# Onion_Omega_Debug_PCB.net
KiCad netlist of a schematic drawn in Altium Designer
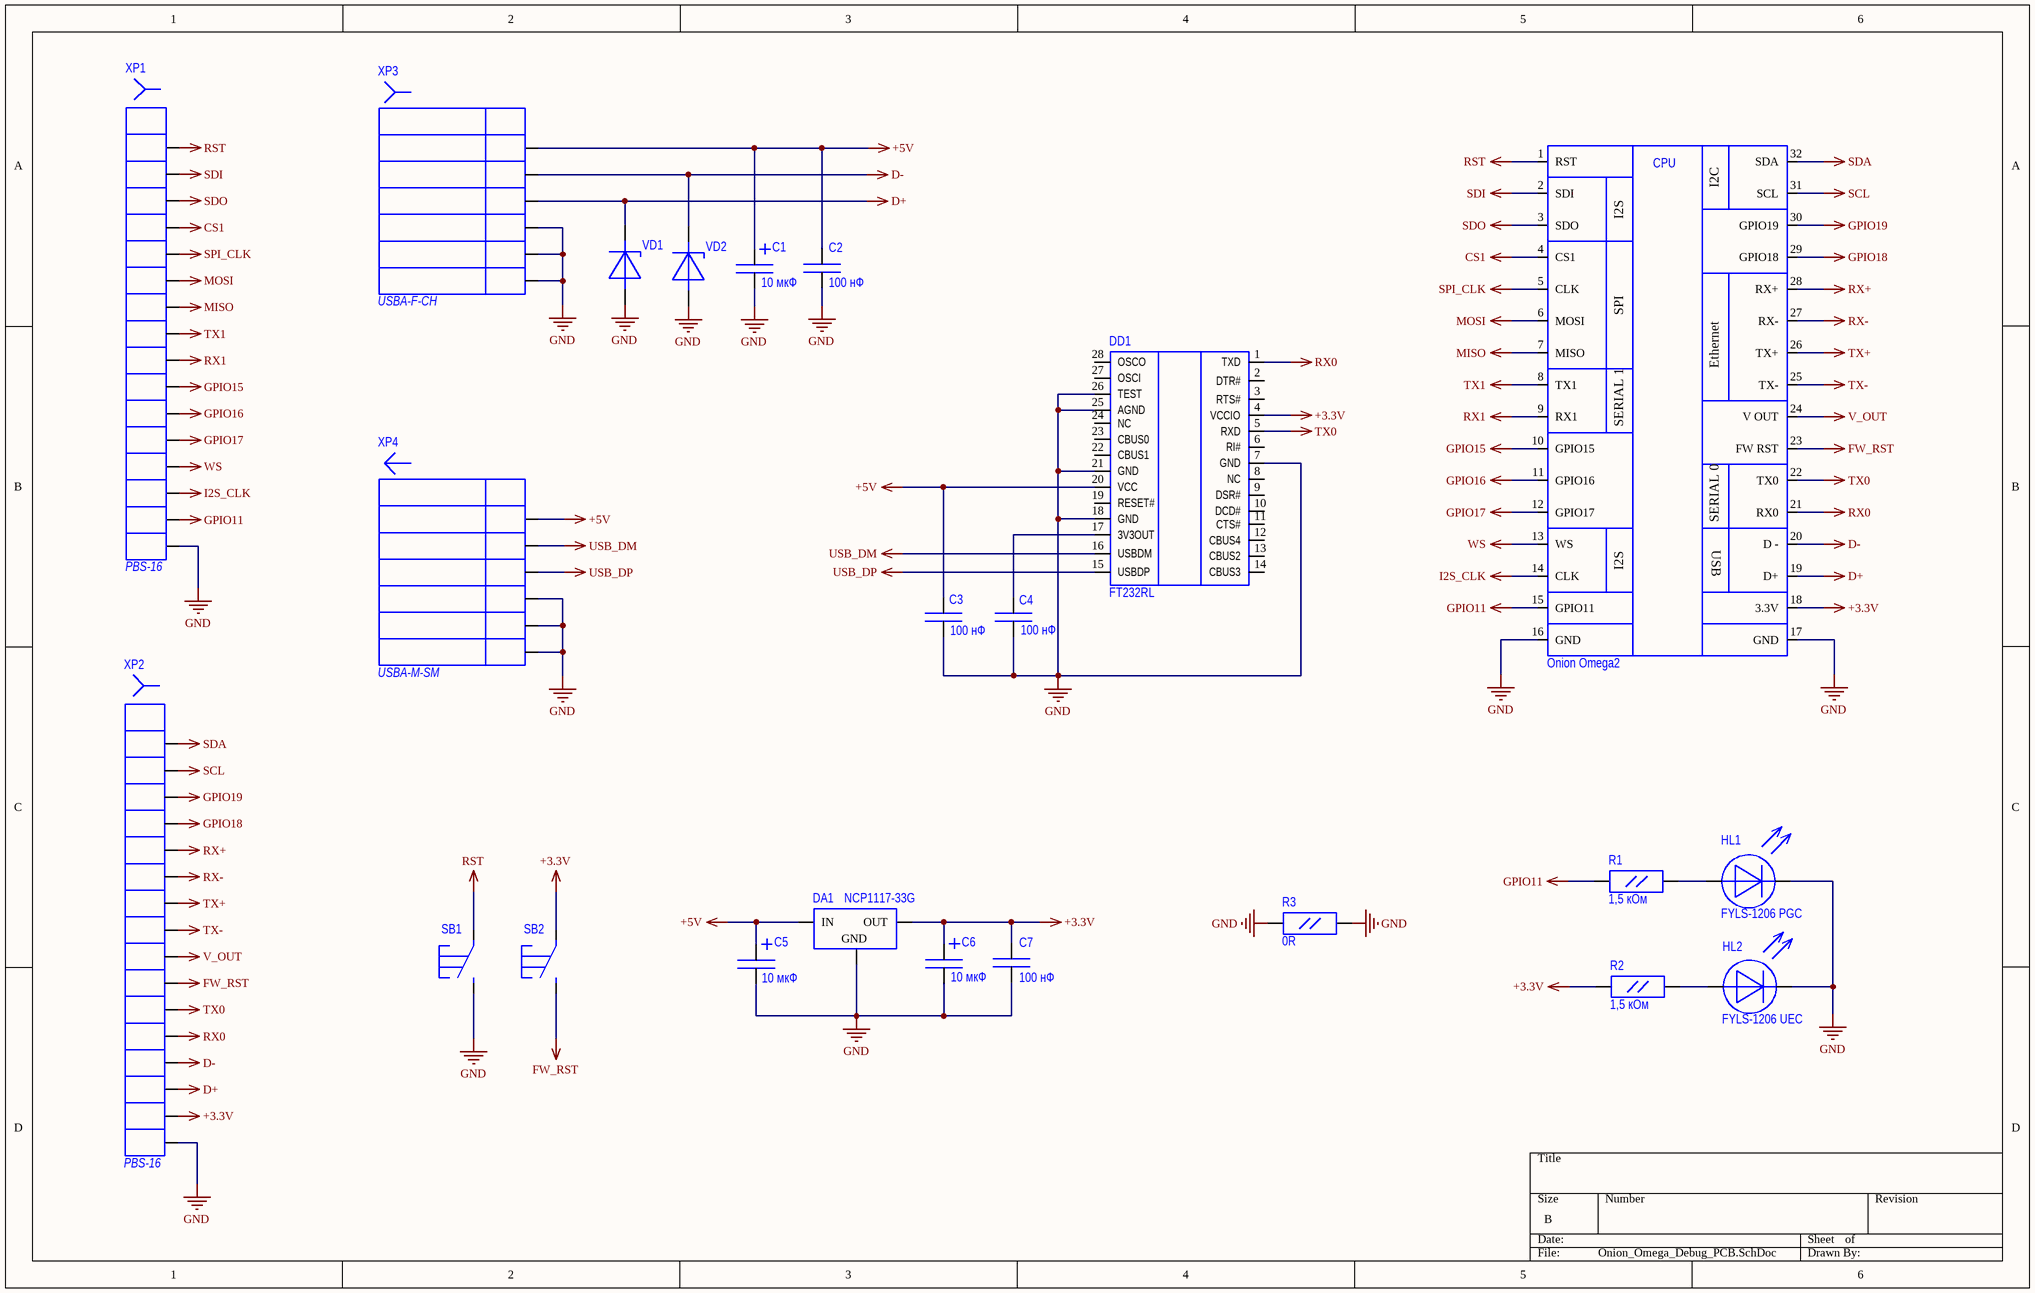
[diagram p0: Onion_Omega_Debug_PCB.SchDoc]

(export (version "E")
  (design (tool "Eeschema 10.0.6"))
  (components
    (comp (ref "C1")
      (value "10 мкФ")
      (footprint "A-case")
      (description "10 мкФ 10 В 10% тип А")
      (fields (field (name "PART NUMBER") "A-case"))
      (libsource (lib "Database") (part "CAPP"))
    )
    (comp (ref "C2")
      (value "100 нФ")
      (footprint "CAP0805")
      (description "100 нФ  5% X7R")
      (libsource (lib "Database") (part "CAP"))
    )
    (comp (ref "C3")
      (value "100 нФ")
      (footprint "CAP0805")
      (description "100 нФ  5% X7R")
      (libsource (lib "Database") (part "CAP"))
    )
    (comp (ref "C4")
      (value "100 нФ")
      (footprint "CAP0805")
      (description "100 нФ  5% X7R")
      (libsource (lib "Database") (part "CAP"))
    )
    (comp (ref "C5")
      (value "10 мкФ")
      (footprint "A-case")
      (description "10 мкФ 10 В 10% тип А")
      (fields (field (name "PART NUMBER") "A-case"))
      (libsource (lib "Database") (part "CAPP"))
    )
    (comp (ref "C6")
      (value "10 мкФ")
      (footprint "A-case")
      (description "10 мкФ 10 В 10% тип А")
      (fields (field (name "PART NUMBER") "A-case"))
      (libsource (lib "Database") (part "CAPP"))
    )
    (comp (ref "C7")
      (value "100 нФ")
      (footprint "CAP0805")
      (description "100 нФ  5% X7R")
      (libsource (lib "Database") (part "CAP"))
    )
    (comp (ref "DA1")
      (value "NCP1117-33G")
      (footprint "D-PAK")
      (libsource (lib "Database") (part "NCP1117-33G"))
    )
    (comp (ref "DD1") (value "FT232RL") (footprint "SSOP-28") (libsource (lib "Database") (part "FT232RL")))
    (comp (ref "HL1")
      (value "FYLS-1206 PGC")
      (footprint "LED 1206 GREEN")
      (description "зеленый сверхяркий")
      (libsource (lib "Database") (part "LED"))
    )
    (comp (ref "HL2")
      (value "FYLS-1206 UЕC")
      (footprint "LED 1206 RED")
      (description "красный")
      (libsource (lib "Database") (part "LED"))
    )
    (comp (ref "OMEGA2")
      (value "Onion Omega2")
      (footprint "Onion_Omega2")
      (libsource (lib "Database") (part "Onion_Omega2"))
    )
    (comp (ref "R1") (value "1,5 кОм") (footprint "RES0805") (libsource (lib "Database") (part "RES 0,125")))
    (comp (ref "R2") (value "1,5 кОм") (footprint "RES0805") (libsource (lib "Database") (part "RES 0,125")))
    (comp (ref "R3")
      (value "0R")
      (footprint "RES0805")
      (description "1,5 кОм")
      (libsource (lib "Database") (part "RES 0,125"))
    )
    (comp (ref "SB1")
      (value "~")
      (footprint "KLS7-TS6606")
      (description "6x6x3.85")
      (fields (field (name "PART NUMBER") "KLS7-TS6606-5.0"))
      (libsource (lib "Database") (part "KLS7-TS6606"))
    )
    (comp (ref "SB2")
      (value "~")
      (footprint "KLS7-TS6606")
      (description "6x6x3.85")
      (fields (field (name "PART NUMBER") "KLS7-TS6606-5.0"))
      (libsource (lib "Database") (part "KLS7-TS6606"))
    )
    (comp (ref "VD1")
      (value "~")
      (footprint "SOT-23")
      (fields (field (name "PART NUMBER") "BZX84-C3V6"))
      (libsource (lib "Database") (part "Zener"))
    )
    (comp (ref "VD2")
      (value "~")
      (footprint "SOT-23")
      (fields (field (name "PART NUMBER") "BZX84-C3V6"))
      (libsource (lib "Database") (part "Zener"))
    )
    (comp (ref "XP1")
      (value "PBS-16")
      (footprint "PBS-16")
      (fields (field (name "PART NUMBER") "PBS-16 2.54mm"))
      (libsource (lib "Database") (part "PBS-16"))
    )
    (comp (ref "XP2")
      (value "PBS-16")
      (footprint "PBS-16")
      (fields (field (name "PART NUMBER") "PBS-16 2.54mm"))
      (libsource (lib "Database") (part "PBS-16"))
    )
    (comp (ref "XP3")
      (value "USBA-F-CH")
      (footprint "USBA-F-CH")
      (fields (field (name "PART NUMBER") "разъем USBA-F-CH"))
      (libsource (lib "Database") (part "USBA-F-CH"))
    )
    (comp (ref "XP4")
      (value "USBA-M-SM")
      (footprint "USBA-M-SM")
      (fields (field (name "PART NUMBER") "разъем USBA-M-SM"))
      (libsource (lib "Database") (part "USBA-M-SM"))
    )
  )
  (nets
    (net (code "1") (name "+3.3V") (class "Default")
      (node (ref "C6") (pin "1") (pinfunction "1_1") (pintype "passive"))
      (node (ref "C7") (pin "1") (pinfunction "1_1") (pintype "passive"))
      (node (ref "DA1") (pin "2") (pinfunction "OUT_2") (pintype "power_in"))
      (node (ref "DD1") (pin "4") (pinfunction "VCCIO_4") (pintype "passive"))
      (node (ref "OMEGA2") (pin "18") (pinfunction "3.3V_18") (pintype "passive"))
      (node (ref "R2") (pin "2") (pinfunction "2_2") (pintype "passive"))
      (node (ref "SB2") (pin "1") (pinfunction "1_1") (pintype "passive"))
      (node (ref "XP2") (pin "15") (pinfunction "15_15") (pintype "passive"))
    )
    (net (code "2") (name "+5V") (class "Default")
      (node (ref "C1") (pin "1") (pinfunction "1_1") (pintype "passive"))
      (node (ref "C2") (pin "1") (pinfunction "1_1") (pintype "passive"))
      (node (ref "C3") (pin "1") (pinfunction "1_1") (pintype "passive"))
      (node (ref "C5") (pin "1") (pinfunction "1_1") (pintype "passive"))
      (node (ref "DA1") (pin "3") (pinfunction "IN_3") (pintype "power_in"))
      (node (ref "DD1") (pin "20") (pinfunction "VCC_20") (pintype "passive"))
      (node (ref "XP3") (pin "1") (pintype "passive"))
      (node (ref "XP4") (pin "1") (pintype "passive"))
    )
    (net (code "3") (name "CS1") (class "Default")
      (node (ref "OMEGA2") (pin "4") (pinfunction "CS1_4") (pintype "passive"))
      (node (ref "XP1") (pin "4") (pinfunction "4_4") (pintype "passive"))
    )
    (net (code "4") (name "D+") (class "Default")
      (node (ref "OMEGA2") (pin "19") (pinfunction "D+_19") (pintype "passive"))
      (node (ref "VD1") (pin "3") (pinfunction "C_3") (pintype "passive"))
      (node (ref "XP2") (pin "14") (pinfunction "14_14") (pintype "passive"))
      (node (ref "XP3") (pin "3") (pintype "passive"))
    )
    (net (code "5") (name "D-") (class "Default")
      (node (ref "OMEGA2") (pin "20") (pinfunction "D_-_20") (pintype "passive"))
      (node (ref "VD2") (pin "3") (pinfunction "C_3") (pintype "passive"))
      (node (ref "XP2") (pin "13") (pinfunction "13_13") (pintype "passive"))
      (node (ref "XP3") (pin "2") (pintype "passive"))
    )
    (net (code "6") (name "FW_RST") (class "Default")
      (node (ref "OMEGA2") (pin "23") (pinfunction "FW_RST_23") (pintype "passive"))
      (node (ref "SB2") (pin "2") (pinfunction "2_2") (pintype "passive"))
      (node (ref "XP2") (pin "10") (pinfunction "10_10") (pintype "passive"))
    )
    (net (code "7") (name "GND") (class "Default")
      (node (ref "C1") (pin "2") (pinfunction "2_2") (pintype "passive"))
      (node (ref "C2") (pin "2") (pinfunction "2_2") (pintype "passive"))
      (node (ref "C3") (pin "2") (pinfunction "2_2") (pintype "passive"))
      (node (ref "C4") (pin "1") (pinfunction "1_1") (pintype "passive"))
      (node (ref "C5") (pin "2") (pinfunction "2_2") (pintype "passive"))
      (node (ref "C6") (pin "2") (pinfunction "2_2") (pintype "passive"))
      (node (ref "C7") (pin "2") (pinfunction "2_2") (pintype "passive"))
      (node (ref "DA1") (pin "1") (pinfunction "GND_1") (pintype "power_in"))
      (node (ref "DD1") (pin "18") (pinfunction "GND_18") (pintype "passive"))
      (node (ref "DD1") (pin "21") (pinfunction "GND_21") (pintype "passive"))
      (node (ref "DD1") (pin "25") (pinfunction "AGND_25") (pintype "passive"))
      (node (ref "DD1") (pin "26") (pinfunction "TEST_26") (pintype "passive"))
      (node (ref "DD1") (pin "7") (pinfunction "GND_7") (pintype "passive"))
      (node (ref "HL1") (pin "2") (pinfunction "C_2") (pintype "passive"))
      (node (ref "HL2") (pin "2") (pinfunction "C_2") (pintype "passive"))
      (node (ref "OMEGA2") (pin "16") (pinfunction "GND_16") (pintype "passive"))
      (node (ref "OMEGA2") (pin "17") (pinfunction "GND_17") (pintype "passive"))
      (node (ref "R3") (pin "1") (pinfunction "1_1") (pintype "passive"))
      (node (ref "R3") (pin "2") (pinfunction "2_2") (pintype "passive"))
      (node (ref "SB1") (pin "2") (pinfunction "2_2") (pintype "passive"))
      (node (ref "VD1") (pin "1") (pinfunction "A_1") (pintype "passive"))
      (node (ref "VD2") (pin "1") (pinfunction "A_1") (pintype "passive"))
      (node (ref "XP1") (pin "16") (pinfunction "16_16") (pintype "passive"))
      (node (ref "XP2") (pin "16") (pinfunction "16_16") (pintype "passive"))
      (node (ref "XP3") (pin "4") (pintype "passive"))
      (node (ref "XP3") (pin "5") (pintype "passive"))
      (node (ref "XP3") (pin "6") (pintype "passive"))
      (node (ref "XP4") (pin "4") (pintype "passive"))
      (node (ref "XP4") (pin "5") (pintype "passive"))
      (node (ref "XP4") (pin "6") (pintype "passive"))
    )
    (net (code "8") (name "GPIO11") (class "Default")
      (node (ref "OMEGA2") (pin "15") (pinfunction "GPIO11_15") (pintype "passive"))
      (node (ref "R1") (pin "1") (pinfunction "1_1") (pintype "passive"))
      (node (ref "XP1") (pin "15") (pinfunction "15_15") (pintype "passive"))
    )
    (net (code "9") (name "GPIO15") (class "Default")
      (node (ref "OMEGA2") (pin "10") (pinfunction "GPIO15_10") (pintype "passive"))
      (node (ref "XP1") (pin "10") (pinfunction "10_10") (pintype "passive"))
    )
    (net (code "10") (name "GPIO16") (class "Default")
      (node (ref "OMEGA2") (pin "11") (pinfunction "GPIO16_11") (pintype "passive"))
      (node (ref "XP1") (pin "11") (pinfunction "11_11") (pintype "passive"))
    )
    (net (code "11") (name "GPIO17") (class "Default")
      (node (ref "OMEGA2") (pin "12") (pinfunction "GPIO17_12") (pintype "passive"))
      (node (ref "XP1") (pin "12") (pinfunction "12_12") (pintype "passive"))
    )
    (net (code "12") (name "GPIO18") (class "Default")
      (node (ref "OMEGA2") (pin "29") (pinfunction "GPIO18_29") (pintype "passive"))
      (node (ref "XP2") (pin "4") (pinfunction "4_4") (pintype "passive"))
    )
    (net (code "13") (name "GPIO19") (class "Default")
      (node (ref "OMEGA2") (pin "30") (pinfunction "GPIO19_30") (pintype "passive"))
      (node (ref "XP2") (pin "3") (pinfunction "3_3") (pintype "passive"))
    )
    (net (code "14") (name "I2S_CLK") (class "Default")
      (node (ref "OMEGA2") (pin "14") (pinfunction "CLK_14") (pintype "passive"))
      (node (ref "XP1") (pin "14") (pinfunction "14_14") (pintype "passive"))
    )
    (net (code "15") (name "MISO") (class "Default")
      (node (ref "OMEGA2") (pin "7") (pinfunction "MISO_7") (pintype "passive"))
      (node (ref "XP1") (pin "7") (pinfunction "7_7") (pintype "passive"))
    )
    (net (code "16") (name "MOSI") (class "Default")
      (node (ref "OMEGA2") (pin "6") (pinfunction "MOSI_6") (pintype "passive"))
      (node (ref "XP1") (pin "6") (pinfunction "6_6") (pintype "passive"))
    )
    (net (code "17") (name "Net-(DD1-3V3OUT)") (class "Default")
      (node (ref "C4") (pin "2") (pinfunction "2_2") (pintype "passive"))
      (node (ref "DD1") (pin "17") (pinfunction "3V3OUT_17") (pintype "passive"))
    )
    (net (code "18") (name "Net-(HL1-A)") (class "Default")
      (node (ref "HL1") (pin "1") (pinfunction "A_1") (pintype "passive"))
      (node (ref "R1") (pin "2") (pinfunction "2_2") (pintype "passive"))
    )
    (net (code "19") (name "Net-(HL2-A)") (class "Default")
      (node (ref "HL2") (pin "1") (pinfunction "A_1") (pintype "passive"))
      (node (ref "R2") (pin "1") (pinfunction "1_1") (pintype "passive"))
    )
    (net (code "20") (name "RST") (class "Default")
      (node (ref "OMEGA2") (pin "1") (pinfunction "RST_1") (pintype "passive"))
      (node (ref "SB1") (pin "1") (pinfunction "1_1") (pintype "passive"))
      (node (ref "XP1") (pin "1") (pinfunction "1_1") (pintype "passive"))
    )
    (net (code "21") (name "RX+") (class "Default")
      (node (ref "OMEGA2") (pin "28") (pinfunction "RX+_28") (pintype "passive"))
      (node (ref "XP2") (pin "5") (pinfunction "5_5") (pintype "passive"))
    )
    (net (code "22") (name "RX-") (class "Default")
      (node (ref "OMEGA2") (pin "27") (pinfunction "RX-_27") (pintype "passive"))
      (node (ref "XP2") (pin "6") (pinfunction "6_6") (pintype "passive"))
    )
    (net (code "23") (name "RX0") (class "Default")
      (node (ref "DD1") (pin "1") (pinfunction "TXD_1") (pintype "passive"))
      (node (ref "OMEGA2") (pin "21") (pinfunction "RX0_21") (pintype "passive"))
      (node (ref "XP2") (pin "12") (pinfunction "12_12") (pintype "passive"))
    )
    (net (code "24") (name "RX1") (class "Default")
      (node (ref "OMEGA2") (pin "9") (pinfunction "RX1_9") (pintype "passive"))
      (node (ref "XP1") (pin "9") (pinfunction "9_9") (pintype "passive"))
    )
    (net (code "25") (name "SCL") (class "Default")
      (node (ref "OMEGA2") (pin "31") (pinfunction "SCL_31") (pintype "passive"))
      (node (ref "XP2") (pin "2") (pinfunction "2_2") (pintype "passive"))
    )
    (net (code "26") (name "SDA") (class "Default")
      (node (ref "OMEGA2") (pin "32") (pinfunction "SDA_32") (pintype "passive"))
      (node (ref "XP2") (pin "1") (pinfunction "1_1") (pintype "passive"))
    )
    (net (code "27") (name "SDI") (class "Default")
      (node (ref "OMEGA2") (pin "2") (pinfunction "SDI_2") (pintype "passive"))
      (node (ref "XP1") (pin "2") (pinfunction "2_2") (pintype "passive"))
    )
    (net (code "28") (name "SDO") (class "Default")
      (node (ref "OMEGA2") (pin "3") (pinfunction "SDO_3") (pintype "passive"))
      (node (ref "XP1") (pin "3") (pinfunction "3_3") (pintype "passive"))
    )
    (net (code "29") (name "SPI_CLK") (class "Default")
      (node (ref "OMEGA2") (pin "5") (pinfunction "CLK_5") (pintype "passive"))
      (node (ref "XP1") (pin "5") (pinfunction "5_5") (pintype "passive"))
    )
    (net (code "30") (name "TX+") (class "Default")
      (node (ref "OMEGA2") (pin "26") (pinfunction "TX+_26") (pintype "passive"))
      (node (ref "XP2") (pin "7") (pinfunction "7_7") (pintype "passive"))
    )
    (net (code "31") (name "TX-") (class "Default")
      (node (ref "OMEGA2") (pin "25") (pinfunction "TX-_25") (pintype "passive"))
      (node (ref "XP2") (pin "8") (pinfunction "8_8") (pintype "passive"))
    )
    (net (code "32") (name "TX0") (class "Default")
      (node (ref "DD1") (pin "5") (pinfunction "RXD_5") (pintype "passive"))
      (node (ref "OMEGA2") (pin "22") (pinfunction "TX0_22") (pintype "passive"))
      (node (ref "XP2") (pin "11") (pinfunction "11_11") (pintype "passive"))
    )
    (net (code "33") (name "TX1") (class "Default")
      (node (ref "OMEGA2") (pin "8") (pinfunction "TX1_8") (pintype "passive"))
      (node (ref "XP1") (pin "8") (pinfunction "8_8") (pintype "passive"))
    )
    (net (code "34") (name "USB_DM") (class "Default")
      (node (ref "DD1") (pin "16") (pinfunction "USBDM_16") (pintype "passive"))
      (node (ref "XP4") (pin "2") (pintype "passive"))
    )
    (net (code "35") (name "USB_DP") (class "Default")
      (node (ref "DD1") (pin "15") (pinfunction "USBDP_15") (pintype "passive"))
      (node (ref "XP4") (pin "3") (pintype "passive"))
    )
    (net (code "36") (name "V_OUT") (class "Default")
      (node (ref "OMEGA2") (pin "24") (pinfunction "V_OUT_24") (pintype "passive"))
      (node (ref "XP2") (pin "9") (pinfunction "9_9") (pintype "passive"))
    )
    (net (code "37") (name "WS") (class "Default")
      (node (ref "OMEGA2") (pin "13") (pinfunction "WS_13") (pintype "passive"))
      (node (ref "XP1") (pin "13") (pinfunction "13_13") (pintype "passive"))
    )
    (net (code "38") (name "unconnected-(DD1-CBUS0-Pad23)") (class "Default")
      (node (ref "DD1") (pin "23") (pinfunction "CBUS0_23") (pintype "passive"))
    )
    (net (code "39") (name "unconnected-(DD1-CBUS1-Pad22)") (class "Default")
      (node (ref "DD1") (pin "22") (pinfunction "CBUS1_22") (pintype "passive"))
    )
    (net (code "40") (name "unconnected-(DD1-CBUS2-Pad13)") (class "Default")
      (node (ref "DD1") (pin "13") (pinfunction "CBUS2_13") (pintype "passive"))
    )
    (net (code "41") (name "unconnected-(DD1-CBUS3-Pad14)") (class "Default")
      (node (ref "DD1") (pin "14") (pinfunction "CBUS3_14") (pintype "passive"))
    )
    (net (code "42") (name "unconnected-(DD1-CBUS4-Pad12)") (class "Default")
      (node (ref "DD1") (pin "12") (pinfunction "CBUS4_12") (pintype "passive"))
    )
    (net (code "43") (name "unconnected-(DD1-CTS#-Pad11)") (class "Default")
      (node (ref "DD1") (pin "11") (pinfunction "CTS#_11") (pintype "passive"))
    )
    (net (code "44") (name "unconnected-(DD1-DCD#-Pad10)") (class "Default")
      (node (ref "DD1") (pin "10") (pinfunction "DCD#_10") (pintype "passive"))
    )
    (net (code "45") (name "unconnected-(DD1-DSR#-Pad9)") (class "Default")
      (node (ref "DD1") (pin "9") (pinfunction "DSR#_9") (pintype "passive"))
    )
    (net (code "46") (name "unconnected-(DD1-DTR#-Pad2)") (class "Default")
      (node (ref "DD1") (pin "2") (pinfunction "DTR#_2") (pintype "passive"))
    )
    (net (code "47") (name "unconnected-(DD1-NC-Pad8)") (class "Default")
      (node (ref "DD1") (pin "8") (pinfunction "NC_8") (pintype "passive"))
    )
    (net (code "48") (name "unconnected-(DD1-NC-Pad24)") (class "Default")
      (node (ref "DD1") (pin "24") (pinfunction "NC_24") (pintype "passive"))
    )
    (net (code "49") (name "unconnected-(DD1-OSCI-Pad27)") (class "Default")
      (node (ref "DD1") (pin "27") (pinfunction "OSCI_27") (pintype "passive"))
    )
    (net (code "50") (name "unconnected-(DD1-OSCO-Pad28)") (class "Default")
      (node (ref "DD1") (pin "28") (pinfunction "OSCO_28") (pintype "passive"))
    )
    (net (code "51") (name "unconnected-(DD1-RESET#-Pad19)") (class "Default")
      (node (ref "DD1") (pin "19") (pinfunction "RESET#_19") (pintype "passive"))
    )
    (net (code "52") (name "unconnected-(DD1-RI#-Pad6)") (class "Default")
      (node (ref "DD1") (pin "6") (pinfunction "RI#_6") (pintype "passive"))
    )
    (net (code "53") (name "unconnected-(DD1-RTS#-Pad3)") (class "Default")
      (node (ref "DD1") (pin "3") (pinfunction "RTS#_3") (pintype "passive"))
    )
  )
)
